# lt_mikro_workshop.net
KiCad netlist of a schematic drawn in EAGLE
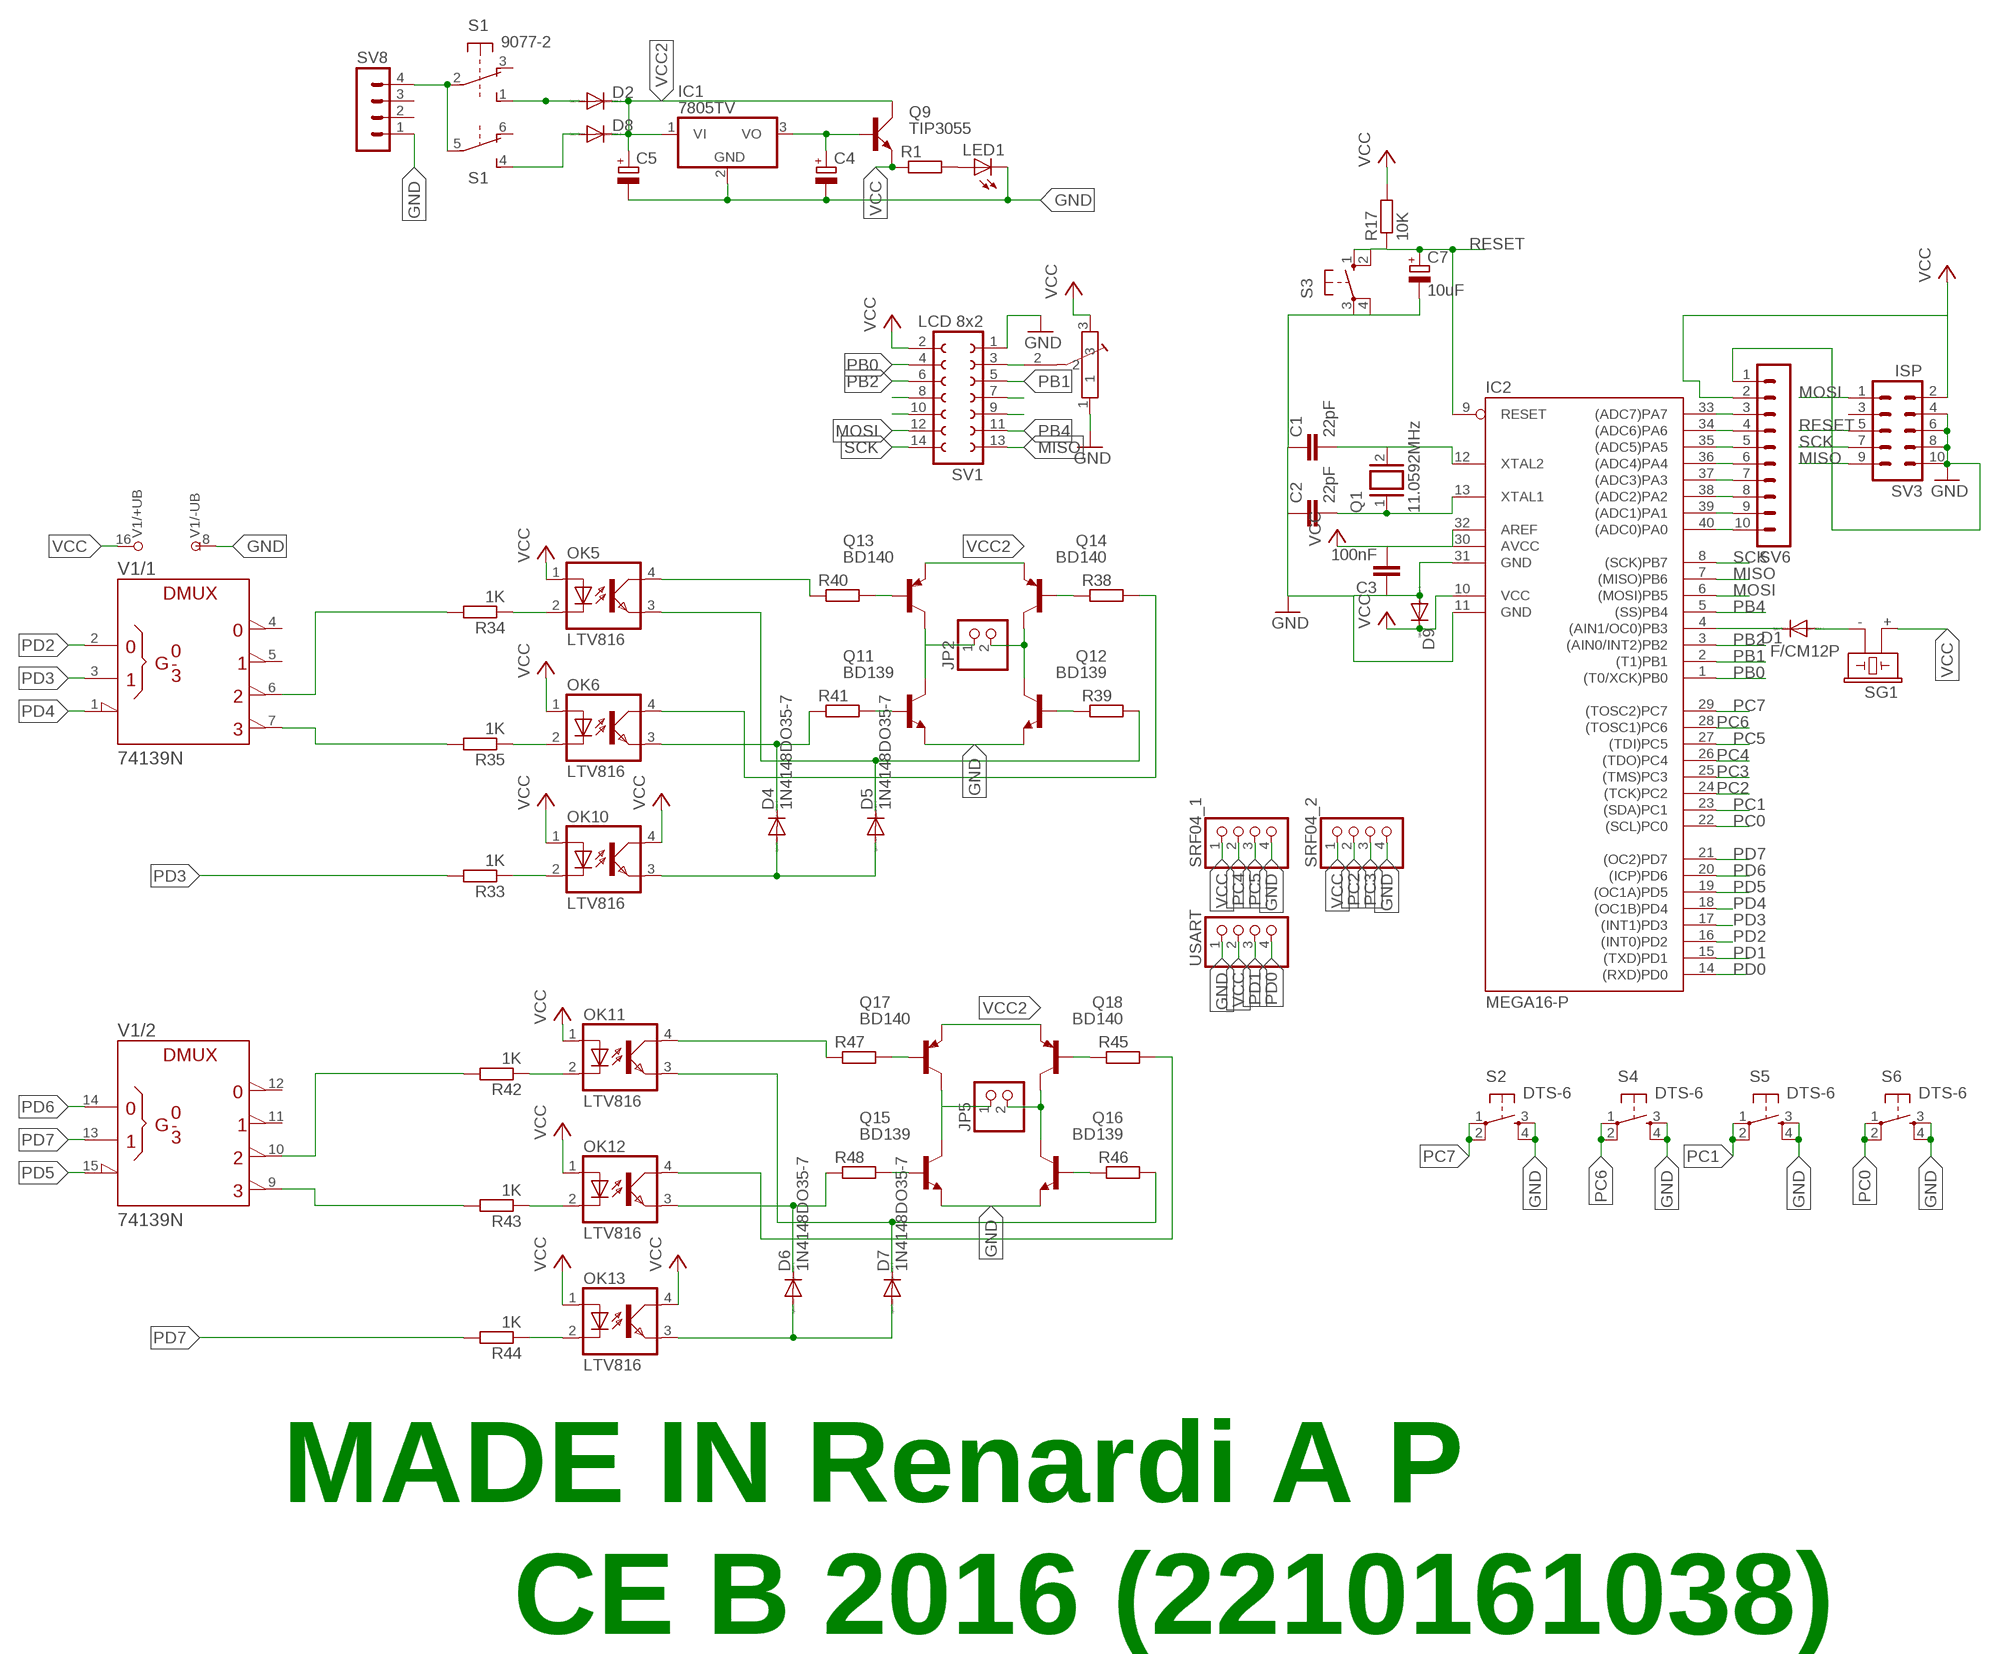
[diagram p0: schematic, sheet 1]

(export (version "E")
  (design (tool "Eeschema 10.0.6"))
  (components
    (comp (ref "C1")
      (value "22pF")
      (footprint "eagle-import:C2.5-2")
      (libsource (lib "eagle-import") (part "C2.5/2"))
    )
    (comp (ref "C2")
      (value "22pF")
      (footprint "eagle-import:C2.5-2")
      (libsource (lib "eagle-import") (part "C2.5/2"))
    )
    (comp (ref "C3")
      (value "100nF")
      (footprint "eagle-import:C2.5-2")
      (libsource (lib "eagle-import") (part "C2.5/2"))
    )
    (comp (ref "C4")
      (value "CPOL-EUE3.5-10")
      (footprint "eagle-import:E3,5-10")
      (libsource (lib "eagle-import") (part "CPOL-EUE3.5-10"))
    )
    (comp (ref "C5")
      (value "CPOL-EUE3.5-10")
      (footprint "eagle-import:E3,5-10")
      (libsource (lib "eagle-import") (part "CPOL-EUE3.5-10"))
    )
    (comp (ref "C7")
      (value "10uF")
      (footprint "eagle-import:E2-5")
      (libsource (lib "eagle-import") (part "CPOL-EUE2-5"))
    )
    (comp (ref "D1")
      (value "DIODE-DO214AA")
      (footprint "eagle-import:DO214AA")
      (libsource (lib "eagle-import") (part "DIODE-DO214AA"))
    )
    (comp (ref "D2")
      (value "DIODE-DO214AA")
      (footprint "eagle-import:DO214AA")
      (libsource (lib "eagle-import") (part "DIODE-DO214AA"))
    )
    (comp (ref "D4")
      (value "1N4148DO35-7")
      (footprint "eagle-import:DO35-7")
      (libsource (lib "eagle-import") (part "1N4148DO35-7"))
    )
    (comp (ref "D5")
      (value "1N4148DO35-7")
      (footprint "eagle-import:DO35-7")
      (libsource (lib "eagle-import") (part "1N4148DO35-7"))
    )
    (comp (ref "D6")
      (value "1N4148DO35-7")
      (footprint "eagle-import:DO35-7")
      (libsource (lib "eagle-import") (part "1N4148DO35-7"))
    )
    (comp (ref "D7")
      (value "1N4148DO35-7")
      (footprint "eagle-import:DO35-7")
      (libsource (lib "eagle-import") (part "1N4148DO35-7"))
    )
    (comp (ref "D8")
      (value "DIODE-DO214AA")
      (footprint "eagle-import:DO214AA")
      (libsource (lib "eagle-import") (part "DIODE-DO214AA"))
    )
    (comp (ref "D9")
      (value "DIODE-DO214AA")
      (footprint "eagle-import:DO214AA")
      (libsource (lib "eagle-import") (part "DIODE-DO214AA"))
    )
    (comp (ref "IC1")
      (value "7805TV")
      (footprint "eagle-import:TO220V")
      (libsource (lib "eagle-import") (part "78TV05"))
    )
    (comp (ref "IC2")
      (value "MEGA16-P")
      (footprint "eagle-import:DIL40")
      (libsource (lib "eagle-import") (part "MEGA16-P"))
    )
    (comp (ref "JP2")
      (value "PINHD-1X2")
      (footprint "eagle-import:1X02")
      (libsource (lib "eagle-import") (part "PINHD-1X2"))
    )
    (comp (ref "JP5")
      (value "PINHD-1X2")
      (footprint "eagle-import:1X02")
      (libsource (lib "eagle-import") (part "PINHD-1X2"))
    )
    (comp (ref "LED1")
      (value "LED3MM")
      (footprint "eagle-import:LED3MM")
      (libsource (lib "eagle-import") (part "LED3MM"))
    )
    (comp (ref "OK5")
      (value "LTV816")
      (footprint "eagle-import:DIL04")
      (libsource (lib "eagle-import") (part "LTV816"))
    )
    (comp (ref "OK6")
      (value "LTV816")
      (footprint "eagle-import:DIL04")
      (libsource (lib "eagle-import") (part "LTV816"))
    )
    (comp (ref "OK10")
      (value "LTV816")
      (footprint "eagle-import:DIL04")
      (libsource (lib "eagle-import") (part "LTV816"))
    )
    (comp (ref "OK11")
      (value "LTV816")
      (footprint "eagle-import:DIL04")
      (libsource (lib "eagle-import") (part "LTV816"))
    )
    (comp (ref "OK12")
      (value "LTV816")
      (footprint "eagle-import:DIL04")
      (libsource (lib "eagle-import") (part "LTV816"))
    )
    (comp (ref "OK13")
      (value "LTV816")
      (footprint "eagle-import:DIL04")
      (libsource (lib "eagle-import") (part "LTV816"))
    )
    (comp (ref "Q1")
      (value "11.0592MHz")
      (footprint "eagle-import:QS")
      (libsource (lib "eagle-import") (part "XTAL/S"))
    )
    (comp (ref "Q9")
      (value "TIP3055")
      (footprint "eagle-import:TOP3AV")
      (libsource (lib "eagle-import") (part "TIP3055"))
    )
    (comp (ref "Q11")
      (value "BD139")
      (footprint "eagle-import:TO126")
      (libsource (lib "eagle-import") (part "BD139"))
    )
    (comp (ref "Q12")
      (value "BD139")
      (footprint "eagle-import:TO126")
      (libsource (lib "eagle-import") (part "BD139"))
    )
    (comp (ref "Q13")
      (value "BD140")
      (footprint "eagle-import:TO126")
      (libsource (lib "eagle-import") (part "BD140"))
    )
    (comp (ref "Q14")
      (value "BD140")
      (footprint "eagle-import:TO126")
      (libsource (lib "eagle-import") (part "BD140"))
    )
    (comp (ref "Q15")
      (value "BD139")
      (footprint "eagle-import:TO126")
      (libsource (lib "eagle-import") (part "BD139"))
    )
    (comp (ref "Q16")
      (value "BD139")
      (footprint "eagle-import:TO126")
      (libsource (lib "eagle-import") (part "BD139"))
    )
    (comp (ref "Q17")
      (value "BD140")
      (footprint "eagle-import:TO126")
      (libsource (lib "eagle-import") (part "BD140"))
    )
    (comp (ref "Q18")
      (value "BD140")
      (footprint "eagle-import:TO126")
      (libsource (lib "eagle-import") (part "BD140"))
    )
    (comp (ref "R1")
      (value "R-EU_0207/7")
      (footprint "eagle-import:0207_7")
      (libsource (lib "eagle-import") (part "R-EU_0207/7"))
    )
    (comp (ref "R17")
      (value "10K")
      (footprint "eagle-import:0204_7")
      (libsource (lib "eagle-import") (part "R-EU_0204/7"))
    )
    (comp (ref "R33")
      (value "1K")
      (footprint "eagle-import:0204_7")
      (libsource (lib "eagle-import") (part "R-EU_0204/7"))
    )
    (comp (ref "R34")
      (value "1K")
      (footprint "eagle-import:0204_7")
      (libsource (lib "eagle-import") (part "R-EU_0204/7"))
    )
    (comp (ref "R35")
      (value "1K")
      (footprint "eagle-import:0204_7")
      (libsource (lib "eagle-import") (part "R-EU_0204/7"))
    )
    (comp (ref "R38")
      (value "R-EU_0207/7")
      (footprint "eagle-import:0207_7")
      (libsource (lib "eagle-import") (part "R-EU_0207/7"))
    )
    (comp (ref "R39")
      (value "R-EU_0207/7")
      (footprint "eagle-import:0207_7")
      (libsource (lib "eagle-import") (part "R-EU_0207/7"))
    )
    (comp (ref "R40")
      (value "R-EU_0207/7")
      (footprint "eagle-import:0207_7")
      (libsource (lib "eagle-import") (part "R-EU_0207/7"))
    )
    (comp (ref "R41")
      (value "R-EU_0207/7")
      (footprint "eagle-import:0207_7")
      (libsource (lib "eagle-import") (part "R-EU_0207/7"))
    )
    (comp (ref "R42")
      (value "1K")
      (footprint "eagle-import:0204_7")
      (libsource (lib "eagle-import") (part "R-EU_0204/7"))
    )
    (comp (ref "R43")
      (value "1K")
      (footprint "eagle-import:0204_7")
      (libsource (lib "eagle-import") (part "R-EU_0204/7"))
    )
    (comp (ref "R44")
      (value "1K")
      (footprint "eagle-import:0204_7")
      (libsource (lib "eagle-import") (part "R-EU_0204/7"))
    )
    (comp (ref "R45")
      (value "R-EU_0207/7")
      (footprint "eagle-import:0207_7")
      (libsource (lib "eagle-import") (part "R-EU_0207/7"))
    )
    (comp (ref "R46")
      (value "R-EU_0207/7")
      (footprint "eagle-import:0207_7")
      (libsource (lib "eagle-import") (part "R-EU_0207/7"))
    )
    (comp (ref "R47")
      (value "R-EU_0207/7")
      (footprint "eagle-import:0207_7")
      (libsource (lib "eagle-import") (part "R-EU_0207/7"))
    )
    (comp (ref "R48")
      (value "R-EU_0207/7")
      (footprint "eagle-import:0207_7")
      (libsource (lib "eagle-import") (part "R-EU_0207/7"))
    )
    (comp (ref "S1")
      (value "9077-2")
      (footprint "eagle-import:9077-2")
      (libsource (lib "eagle-import") (part "9077-2"))
    )
    (comp (ref "S2")
      (value "DTS-6")
      (footprint "eagle-import:DTS-6")
      (libsource (lib "eagle-import") (part "DTS-6"))
    )
    (comp (ref "S3")
      (value "10-XX")
      (footprint "eagle-import:B3F-10XX")
      (libsource (lib "eagle-import") (part "10-XX"))
    )
    (comp (ref "S4")
      (value "DTS-6")
      (footprint "eagle-import:DTS-6")
      (libsource (lib "eagle-import") (part "DTS-6"))
    )
    (comp (ref "S5")
      (value "DTS-6")
      (footprint "eagle-import:DTS-6")
      (libsource (lib "eagle-import") (part "DTS-6"))
    )
    (comp (ref "S6")
      (value "DTS-6")
      (footprint "eagle-import:DTS-6")
      (libsource (lib "eagle-import") (part "DTS-6"))
    )
    (comp (ref "SG1")
      (value "F/CM12P")
      (footprint "eagle-import:F_CM12P")
      (libsource (lib "eagle-import") (part "F/CM12P"))
    )
    (comp (ref "SRF04_1")
      (value "PINHD-1X4")
      (footprint "eagle-import:1X04")
      (libsource (lib "eagle-import") (part "PINHD-1X4"))
    )
    (comp (ref "SRF04_2")
      (value "PINHD-1X4")
      (footprint "eagle-import:1X04")
      (libsource (lib "eagle-import") (part "PINHD-1X4"))
    )
    (comp (ref "SV1")
      (value "LCD 8x2")
      (footprint "eagle-import:FE07-2")
      (libsource (lib "eagle-import") (part "FE07-2"))
    )
    (comp (ref "SV3")
      (value "ISP")
      (footprint "eagle-import:MA05-2")
      (libsource (lib "eagle-import") (part "MA05-2"))
    )
    (comp (ref "SV6")
      (value "MA10-1")
      (footprint "eagle-import:MA10-1")
      (libsource (lib "eagle-import") (part "MA10-1"))
    )
    (comp (ref "SV8")
      (value "MA04-1")
      (footprint "eagle-import:MA04-1")
      (libsource (lib "eagle-import") (part "MA04-1"))
    )
    (comp (ref "U$1")
      (value "TRIMPOT")
      (footprint "eagle-import:TRIMPOT")
      (libsource (lib "eagle-import") (part "TRIMPOT"))
    )
    (comp (ref "USART")
      (value "PINHD-1X4")
      (footprint "eagle-import:1X04")
      (libsource (lib "eagle-import") (part "PINHD-1X4"))
    )
    (comp (ref "V1")
      (value "74139N")
      (footprint "eagle-import:DIL16")
      (libsource (lib "eagle-import") (part "74139N"))
    )
  )
  (nets
    (net (code "1") (name "/RESET") (class "Default")
      (node (ref "C7") (pin "+") (pinfunction "+_+") (pintype "passive"))
      (node (ref "IC2") (pin "9") (pinfunction "RESET_9") (pintype "input"))
      (node (ref "R17") (pin "1") (pinfunction "1_1") (pintype "passive"))
      (node (ref "S3") (pin "1") (pinfunction "S_1") (pintype "passive"))
      (node (ref "S3") (pin "2") (pinfunction "S1_2") (pintype "passive"))
      (node (ref "SV3") (pin "5") (pinfunction "5_5") (pintype "passive"))
    )
    (net (code "2") (name "GND") (class "Default")
      (node (ref "C1") (pin "1") (pinfunction "1_1") (pintype "passive"))
      (node (ref "C2") (pin "1") (pinfunction "1_1") (pintype "passive"))
      (node (ref "C3") (pin "1") (pinfunction "1_1") (pintype "passive"))
      (node (ref "C4") (pin "-") (pinfunction "-_-") (pintype "passive"))
      (node (ref "C5") (pin "-") (pinfunction "-_-") (pintype "passive"))
      (node (ref "C7") (pin "-") (pinfunction "-_-") (pintype "passive"))
      (node (ref "D9") (pin "A") (pinfunction "A_A") (pintype "passive"))
      (node (ref "IC1") (pin "2") (pinfunction "GND_2") (pintype "passive"))
      (node (ref "IC2") (pin "11") (pinfunction "GND_11") (pintype "power_in"))
      (node (ref "IC2") (pin "31") (pinfunction "GND_31") (pintype "power_in"))
      (node (ref "LED1") (pin "K") (pinfunction "C_K") (pintype "passive"))
      (node (ref "Q11") (pin "1") (pinfunction "E_1") (pintype "passive"))
      (node (ref "Q12") (pin "1") (pinfunction "E_1") (pintype "passive"))
      (node (ref "Q15") (pin "1") (pinfunction "E_1") (pintype "passive"))
      (node (ref "Q16") (pin "1") (pinfunction "E_1") (pintype "passive"))
      (node (ref "S2") (pin "3") (pinfunction "3_3") (pintype "passive"))
      (node (ref "S2") (pin "4") (pinfunction "4_4") (pintype "passive"))
      (node (ref "S3") (pin "3") (pinfunction "P_3") (pintype "passive"))
      (node (ref "S3") (pin "4") (pinfunction "P1_4") (pintype "passive"))
      (node (ref "S4") (pin "3") (pinfunction "3_3") (pintype "passive"))
      (node (ref "S4") (pin "4") (pinfunction "4_4") (pintype "passive"))
      (node (ref "S5") (pin "3") (pinfunction "3_3") (pintype "passive"))
      (node (ref "S5") (pin "4") (pinfunction "4_4") (pintype "passive"))
      (node (ref "S6") (pin "3") (pinfunction "3_3") (pintype "passive"))
      (node (ref "S6") (pin "4") (pinfunction "4_4") (pintype "passive"))
      (node (ref "SRF04_1") (pin "4") (pinfunction "4_4") (pintype "passive"))
      (node (ref "SRF04_2") (pin "4") (pinfunction "4_4") (pintype "passive"))
      (node (ref "SV1") (pin "1") (pinfunction "1_1") (pintype "passive"))
      (node (ref "SV3") (pin "10") (pinfunction "10_10") (pintype "passive"))
      (node (ref "SV3") (pin "4") (pinfunction "4_4") (pintype "passive"))
      (node (ref "SV3") (pin "6") (pinfunction "6_6") (pintype "passive"))
      (node (ref "SV3") (pin "8") (pinfunction "8_8") (pintype "passive"))
      (node (ref "SV6") (pin "1") (pinfunction "1_1") (pintype "passive"))
      (node (ref "SV8") (pin "1") (pinfunction "1_1") (pintype "passive"))
      (node (ref "U$1") (pin "1") (pinfunction "1_1") (pintype "bidirectional"))
      (node (ref "USART") (pin "1") (pinfunction "1_1") (pintype "passive"))
      (node (ref "V1") (pin "8") (pinfunction "-UB_8") (pintype "power_in"))
    )
    (net (code "3") (name "MISO") (class "Default")
      (node (ref "IC2") (pin "7") (pinfunction "(MISO)PB6_7") (pintype "bidirectional"))
      (node (ref "SV1") (pin "13") (pinfunction "13_13") (pintype "passive"))
      (node (ref "SV3") (pin "9") (pinfunction "9_9") (pintype "passive"))
    )
    (net (code "4") (name "MOSI") (class "Default")
      (node (ref "IC2") (pin "6") (pinfunction "(MOSI)PB5_6") (pintype "bidirectional"))
      (node (ref "SV1") (pin "12") (pinfunction "12_12") (pintype "passive"))
      (node (ref "SV3") (pin "1") (pinfunction "1_1") (pintype "passive"))
    )
    (net (code "5") (name "Net-(IC1-VO)") (class "Default")
      (node (ref "C4") (pin "+") (pinfunction "+_+") (pintype "passive"))
      (node (ref "IC1") (pin "3") (pinfunction "VO_3") (pintype "passive"))
      (node (ref "Q9") (pin "B") (pinfunction "B_B") (pintype "passive"))
    )
    (net (code "6") (name "Net-(IC2-(ADC0)PA0)") (class "Default")
      (node (ref "IC2") (pin "40") (pinfunction "(ADC0)PA0_40") (pintype "bidirectional"))
      (node (ref "SV6") (pin "10") (pinfunction "10_10") (pintype "passive"))
    )
    (net (code "7") (name "Net-(IC2-(ADC1)PA1)") (class "Default")
      (node (ref "IC2") (pin "39") (pinfunction "(ADC1)PA1_39") (pintype "bidirectional"))
      (node (ref "SV6") (pin "9") (pinfunction "9_9") (pintype "passive"))
    )
    (net (code "8") (name "Net-(IC2-(ADC2)PA2)") (class "Default")
      (node (ref "IC2") (pin "38") (pinfunction "(ADC2)PA2_38") (pintype "bidirectional"))
      (node (ref "SV6") (pin "8") (pinfunction "8_8") (pintype "passive"))
    )
    (net (code "9") (name "Net-(IC2-(ADC3)PA3)") (class "Default")
      (node (ref "IC2") (pin "37") (pinfunction "(ADC3)PA3_37") (pintype "bidirectional"))
      (node (ref "SV6") (pin "7") (pinfunction "7_7") (pintype "passive"))
    )
    (net (code "10") (name "Net-(IC2-(ADC4)PA4)") (class "Default")
      (node (ref "IC2") (pin "36") (pinfunction "(ADC4)PA4_36") (pintype "bidirectional"))
      (node (ref "SV6") (pin "6") (pinfunction "6_6") (pintype "passive"))
    )
    (net (code "11") (name "Net-(IC2-(ADC5)PA5)") (class "Default")
      (node (ref "IC2") (pin "35") (pinfunction "(ADC5)PA5_35") (pintype "bidirectional"))
      (node (ref "SV6") (pin "5") (pinfunction "5_5") (pintype "passive"))
    )
    (net (code "12") (name "Net-(IC2-(ADC6)PA6)") (class "Default")
      (node (ref "IC2") (pin "34") (pinfunction "(ADC6)PA6_34") (pintype "bidirectional"))
      (node (ref "SV6") (pin "4") (pinfunction "4_4") (pintype "passive"))
    )
    (net (code "13") (name "Net-(IC2-(ADC7)PA7)") (class "Default")
      (node (ref "IC2") (pin "33") (pinfunction "(ADC7)PA7_33") (pintype "bidirectional"))
      (node (ref "SV6") (pin "3") (pinfunction "3_3") (pintype "passive"))
    )
    (net (code "14") (name "Net-(IC2-(AIN1{slash}OC0)PB3)") (class "Default")
      (node (ref "D1") (pin "C") (pinfunction "C_C") (pintype "passive"))
      (node (ref "IC2") (pin "4") (pinfunction "(AIN1/OC0)PB3_4") (pintype "bidirectional"))
    )
    (net (code "15") (name "Net-(IC2-XTAL1)") (class "Default")
      (node (ref "C2") (pin "2") (pinfunction "2_2") (pintype "passive"))
      (node (ref "IC2") (pin "13") (pinfunction "XTAL1_13") (pintype "bidirectional"))
      (node (ref "Q1") (pin "1") (pinfunction "1_1") (pintype "passive"))
    )
    (net (code "16") (name "Net-(IC2-XTAL2)") (class "Default")
      (node (ref "C1") (pin "2") (pinfunction "2_2") (pintype "passive"))
      (node (ref "IC2") (pin "12") (pinfunction "XTAL2_12") (pintype "bidirectional"))
      (node (ref "Q1") (pin "2") (pinfunction "2_2") (pintype "passive"))
    )
    (net (code "17") (name "Net-(LED1-PadA)") (class "Default")
      (node (ref "LED1") (pin "A") (pinfunction "A_A") (pintype "passive"))
      (node (ref "R1") (pin "2") (pinfunction "2_2") (pintype "passive"))
    )
    (net (code "18") (name "Net-(OK5-C)") (class "Default")
      (node (ref "OK5") (pin "2") (pinfunction "C_2") (pintype "passive"))
      (node (ref "R34") (pin "1") (pinfunction "1_1") (pintype "passive"))
    )
    (net (code "19") (name "Net-(OK5-COL)") (class "Default")
      (node (ref "OK5") (pin "4") (pinfunction "COL_4") (pintype "passive"))
      (node (ref "R40") (pin "1") (pinfunction "1_1") (pintype "passive"))
    )
    (net (code "20") (name "Net-(OK5-EMIT)") (class "Default")
      (node (ref "D5") (pin "C") (pinfunction "C_C") (pintype "passive"))
      (node (ref "OK5") (pin "3") (pinfunction "EMIT_3") (pintype "passive"))
      (node (ref "R39") (pin "2") (pinfunction "2_2") (pintype "passive"))
    )
    (net (code "21") (name "Net-(OK6-C)") (class "Default")
      (node (ref "OK6") (pin "2") (pinfunction "C_2") (pintype "passive"))
      (node (ref "R35") (pin "1") (pinfunction "1_1") (pintype "passive"))
    )
    (net (code "22") (name "Net-(OK6-COL)") (class "Default")
      (node (ref "OK6") (pin "4") (pinfunction "COL_4") (pintype "passive"))
      (node (ref "R38") (pin "2") (pinfunction "2_2") (pintype "passive"))
    )
    (net (code "23") (name "Net-(OK6-EMIT)") (class "Default")
      (node (ref "D4") (pin "C") (pinfunction "C_C") (pintype "passive"))
      (node (ref "OK6") (pin "3") (pinfunction "EMIT_3") (pintype "passive"))
      (node (ref "R41") (pin "1") (pinfunction "1_1") (pintype "passive"))
    )
    (net (code "24") (name "Net-(OK10-C)") (class "Default")
      (node (ref "OK10") (pin "2") (pinfunction "C_2") (pintype "passive"))
      (node (ref "R33") (pin "1") (pinfunction "1_1") (pintype "passive"))
    )
    (net (code "25") (name "Net-(OK10-EMIT)") (class "Default")
      (node (ref "D4") (pin "A") (pinfunction "A_A") (pintype "passive"))
      (node (ref "D5") (pin "A") (pinfunction "A_A") (pintype "passive"))
      (node (ref "OK10") (pin "3") (pinfunction "EMIT_3") (pintype "passive"))
    )
    (net (code "26") (name "Net-(OK11-C)") (class "Default")
      (node (ref "OK11") (pin "2") (pinfunction "C_2") (pintype "passive"))
      (node (ref "R42") (pin "1") (pinfunction "1_1") (pintype "passive"))
    )
    (net (code "27") (name "Net-(OK11-COL)") (class "Default")
      (node (ref "OK11") (pin "4") (pinfunction "COL_4") (pintype "passive"))
      (node (ref "R47") (pin "1") (pinfunction "1_1") (pintype "passive"))
    )
    (net (code "28") (name "Net-(OK11-EMIT)") (class "Default")
      (node (ref "D7") (pin "C") (pinfunction "C_C") (pintype "passive"))
      (node (ref "OK11") (pin "3") (pinfunction "EMIT_3") (pintype "passive"))
      (node (ref "R46") (pin "2") (pinfunction "2_2") (pintype "passive"))
    )
    (net (code "29") (name "Net-(OK12-C)") (class "Default")
      (node (ref "OK12") (pin "2") (pinfunction "C_2") (pintype "passive"))
      (node (ref "R43") (pin "1") (pinfunction "1_1") (pintype "passive"))
    )
    (net (code "30") (name "Net-(OK12-COL)") (class "Default")
      (node (ref "OK12") (pin "4") (pinfunction "COL_4") (pintype "passive"))
      (node (ref "R45") (pin "2") (pinfunction "2_2") (pintype "passive"))
    )
    (net (code "31") (name "Net-(OK12-EMIT)") (class "Default")
      (node (ref "D6") (pin "C") (pinfunction "C_C") (pintype "passive"))
      (node (ref "OK12") (pin "3") (pinfunction "EMIT_3") (pintype "passive"))
      (node (ref "R48") (pin "1") (pinfunction "1_1") (pintype "passive"))
    )
    (net (code "32") (name "Net-(OK13-C)") (class "Default")
      (node (ref "OK13") (pin "2") (pinfunction "C_2") (pintype "passive"))
      (node (ref "R44") (pin "1") (pinfunction "1_1") (pintype "passive"))
    )
    (net (code "33") (name "Net-(OK13-EMIT)") (class "Default")
      (node (ref "D6") (pin "A") (pinfunction "A_A") (pintype "passive"))
      (node (ref "D7") (pin "A") (pinfunction "A_A") (pintype "passive"))
      (node (ref "OK13") (pin "3") (pinfunction "EMIT_3") (pintype "passive"))
    )
    (net (code "34") (name "Net-(Q11-B)") (class "Default")
      (node (ref "Q11") (pin "3") (pinfunction "B_3") (pintype "passive"))
      (node (ref "R41") (pin "2") (pinfunction "2_2") (pintype "passive"))
    )
    (net (code "35") (name "Net-(Q11-C)") (class "Default")
      (node (ref "JP2") (pin "1") (pinfunction "1_1") (pintype "passive"))
      (node (ref "Q11") (pin "2") (pinfunction "C_2") (pintype "passive"))
      (node (ref "Q13") (pin "2") (pinfunction "C_2") (pintype "passive"))
    )
    (net (code "36") (name "Net-(Q12-B)") (class "Default")
      (node (ref "Q12") (pin "3") (pinfunction "B_3") (pintype "passive"))
      (node (ref "R39") (pin "1") (pinfunction "1_1") (pintype "passive"))
    )
    (net (code "37") (name "Net-(Q12-C)") (class "Default")
      (node (ref "JP2") (pin "2") (pinfunction "2_2") (pintype "passive"))
      (node (ref "Q12") (pin "2") (pinfunction "C_2") (pintype "passive"))
      (node (ref "Q14") (pin "2") (pinfunction "C_2") (pintype "passive"))
    )
    (net (code "38") (name "Net-(Q13-B)") (class "Default")
      (node (ref "Q13") (pin "3") (pinfunction "B_3") (pintype "passive"))
      (node (ref "R40") (pin "2") (pinfunction "2_2") (pintype "passive"))
    )
    (net (code "39") (name "Net-(Q14-B)") (class "Default")
      (node (ref "Q14") (pin "3") (pinfunction "B_3") (pintype "passive"))
      (node (ref "R38") (pin "1") (pinfunction "1_1") (pintype "passive"))
    )
    (net (code "40") (name "Net-(Q15-B)") (class "Default")
      (node (ref "Q15") (pin "3") (pinfunction "B_3") (pintype "passive"))
      (node (ref "R48") (pin "2") (pinfunction "2_2") (pintype "passive"))
    )
    (net (code "41") (name "Net-(Q15-C)") (class "Default")
      (node (ref "JP5") (pin "1") (pinfunction "1_1") (pintype "passive"))
      (node (ref "Q15") (pin "2") (pinfunction "C_2") (pintype "passive"))
      (node (ref "Q17") (pin "2") (pinfunction "C_2") (pintype "passive"))
    )
    (net (code "42") (name "Net-(Q16-B)") (class "Default")
      (node (ref "Q16") (pin "3") (pinfunction "B_3") (pintype "passive"))
      (node (ref "R46") (pin "1") (pinfunction "1_1") (pintype "passive"))
    )
    (net (code "43") (name "Net-(Q16-C)") (class "Default")
      (node (ref "JP5") (pin "2") (pinfunction "2_2") (pintype "passive"))
      (node (ref "Q16") (pin "2") (pinfunction "C_2") (pintype "passive"))
      (node (ref "Q18") (pin "2") (pinfunction "C_2") (pintype "passive"))
    )
    (net (code "44") (name "Net-(Q17-B)") (class "Default")
      (node (ref "Q17") (pin "3") (pinfunction "B_3") (pintype "passive"))
      (node (ref "R47") (pin "2") (pinfunction "2_2") (pintype "passive"))
    )
    (net (code "45") (name "Net-(Q18-B)") (class "Default")
      (node (ref "Q18") (pin "3") (pinfunction "B_3") (pintype "passive"))
      (node (ref "R45") (pin "1") (pinfunction "1_1") (pintype "passive"))
    )
    (net (code "46") (name "Net-(S1A-P)") (class "Default")
      (node (ref "S1") (pin "2") (pinfunction "P_2") (pintype "passive"))
      (node (ref "S1") (pin "5") (pinfunction "P_5") (pintype "passive"))
      (node (ref "SV8") (pin "4") (pinfunction "4_4") (pintype "passive"))
    )
    (net (code "47") (name "Net-(S1A-S)") (class "Default")
      (node (ref "D2") (pin "A") (pinfunction "A_A") (pintype "passive"))
      (node (ref "S1") (pin "1") (pinfunction "S_1") (pintype "passive"))
    )
    (net (code "48") (name "Net-(S1B-S)") (class "Default")
      (node (ref "D8") (pin "A") (pinfunction "A_A") (pintype "passive"))
      (node (ref "S1") (pin "4") (pinfunction "S_4") (pintype "passive"))
    )
    (net (code "49") (name "Net-(SG1-2)") (class "Default")
      (node (ref "D1") (pin "A") (pinfunction "A_A") (pintype "passive"))
      (node (ref "SG1") (pin "-") (pinfunction "2_-") (pintype "passive"))
    )
    (net (code "50") (name "Net-(V1C-Y2)") (class "Default")
      (node (ref "R34") (pin "2") (pinfunction "2_2") (pintype "passive"))
      (node (ref "V1") (pin "6") (pinfunction "Y2_6") (pintype "output"))
    )
    (net (code "51") (name "Net-(V1C-Y3)") (class "Default")
      (node (ref "R35") (pin "2") (pinfunction "2_2") (pintype "passive"))
      (node (ref "V1") (pin "7") (pinfunction "Y3_7") (pintype "output"))
    )
    (net (code "52") (name "Net-(V1D-Y2)") (class "Default")
      (node (ref "R42") (pin "2") (pinfunction "2_2") (pintype "passive"))
      (node (ref "V1") (pin "10") (pinfunction "Y2_10") (pintype "output"))
    )
    (net (code "53") (name "Net-(V1D-Y3)") (class "Default")
      (node (ref "R43") (pin "2") (pinfunction "2_2") (pintype "passive"))
      (node (ref "V1") (pin "9") (pinfunction "Y3_9") (pintype "output"))
    )
    (net (code "54") (name "PB0") (class "Default")
      (node (ref "IC2") (pin "1") (pinfunction "(T0/XCK)PB0_1") (pintype "bidirectional"))
      (node (ref "SV1") (pin "3") (pinfunction "3_3") (pintype "passive"))
      (node (ref "SV1") (pin "4") (pinfunction "4_4") (pintype "passive"))
      (node (ref "U$1") (pin "2") (pinfunction "2_2") (pintype "bidirectional"))
    )
    (net (code "55") (name "PB1") (class "Default")
      (node (ref "IC2") (pin "2") (pinfunction "(T1)PB1_2") (pintype "bidirectional"))
      (node (ref "SV1") (pin "5") (pinfunction "5_5") (pintype "passive"))
    )
    (net (code "56") (name "PB2") (class "Default")
      (node (ref "IC2") (pin "3") (pinfunction "(AIN0/INT2)PB2_3") (pintype "bidirectional"))
      (node (ref "SV1") (pin "6") (pinfunction "6_6") (pintype "passive"))
    )
    (net (code "57") (name "PB4") (class "Default")
      (node (ref "IC2") (pin "5") (pinfunction "(SS)PB4_5") (pintype "bidirectional"))
      (node (ref "SV1") (pin "11") (pinfunction "11_11") (pintype "passive"))
    )
    (net (code "58") (name "PC0") (class "Default")
      (node (ref "IC2") (pin "22") (pinfunction "(SCL)PC0_22") (pintype "bidirectional"))
      (node (ref "S6") (pin "1") (pinfunction "1_1") (pintype "passive"))
      (node (ref "S6") (pin "2") (pinfunction "2_2") (pintype "passive"))
    )
    (net (code "59") (name "PC1") (class "Default")
      (node (ref "IC2") (pin "23") (pinfunction "(SDA)PC1_23") (pintype "bidirectional"))
      (node (ref "S5") (pin "1") (pinfunction "1_1") (pintype "passive"))
      (node (ref "S5") (pin "2") (pinfunction "2_2") (pintype "passive"))
    )
    (net (code "60") (name "PC2") (class "Default")
      (node (ref "IC2") (pin "24") (pinfunction "(TCK)PC2_24") (pintype "bidirectional"))
      (node (ref "SRF04_2") (pin "2") (pinfunction "2_2") (pintype "passive"))
    )
    (net (code "61") (name "PC3") (class "Default")
      (node (ref "IC2") (pin "25") (pinfunction "(TMS)PC3_25") (pintype "bidirectional"))
      (node (ref "SRF04_2") (pin "3") (pinfunction "3_3") (pintype "passive"))
    )
    (net (code "62") (name "PC4") (class "Default")
      (node (ref "IC2") (pin "26") (pinfunction "(TDO)PC4_26") (pintype "bidirectional"))
      (node (ref "SRF04_1") (pin "2") (pinfunction "2_2") (pintype "passive"))
    )
    (net (code "63") (name "PC5") (class "Default")
      (node (ref "IC2") (pin "27") (pinfunction "(TDI)PC5_27") (pintype "bidirectional"))
      (node (ref "SRF04_1") (pin "3") (pinfunction "3_3") (pintype "passive"))
    )
    (net (code "64") (name "PC6") (class "Default")
      (node (ref "IC2") (pin "28") (pinfunction "(TOSC1)PC6_28") (pintype "bidirectional"))
      (node (ref "S4") (pin "1") (pinfunction "1_1") (pintype "passive"))
      (node (ref "S4") (pin "2") (pinfunction "2_2") (pintype "passive"))
    )
    (net (code "65") (name "PC7") (class "Default")
      (node (ref "IC2") (pin "29") (pinfunction "(TOSC2)PC7_29") (pintype "bidirectional"))
      (node (ref "S2") (pin "1") (pinfunction "1_1") (pintype "passive"))
      (node (ref "S2") (pin "2") (pinfunction "2_2") (pintype "passive"))
    )
    (net (code "66") (name "PD0") (class "Default")
      (node (ref "IC2") (pin "14") (pinfunction "(RXD)PD0_14") (pintype "bidirectional"))
      (node (ref "USART") (pin "4") (pinfunction "4_4") (pintype "passive"))
    )
    (net (code "67") (name "PD1") (class "Default")
      (node (ref "IC2") (pin "15") (pinfunction "(TXD)PD1_15") (pintype "bidirectional"))
      (node (ref "USART") (pin "3") (pinfunction "3_3") (pintype "passive"))
    )
    (net (code "68") (name "PD2") (class "Default")
      (node (ref "IC2") (pin "16") (pinfunction "(INT0)PD2_16") (pintype "bidirectional"))
      (node (ref "V1") (pin "2") (pinfunction "A_2") (pintype "input"))
    )
    (net (code "69") (name "PD3") (class "Default")
      (node (ref "IC2") (pin "17") (pinfunction "(INT1)PD3_17") (pintype "bidirectional"))
      (node (ref "R33") (pin "2") (pinfunction "2_2") (pintype "passive"))
      (node (ref "V1") (pin "3") (pinfunction "B_3") (pintype "input"))
    )
    (net (code "70") (name "PD4") (class "Default")
      (node (ref "IC2") (pin "18") (pinfunction "(OC1B)PD4_18") (pintype "bidirectional"))
      (node (ref "V1") (pin "1") (pinfunction "~{G}_1") (pintype "input"))
    )
    (net (code "71") (name "PD5") (class "Default")
      (node (ref "IC2") (pin "19") (pinfunction "(OC1A)PD5_19") (pintype "bidirectional"))
      (node (ref "V1") (pin "15") (pinfunction "~{G}_15") (pintype "input"))
    )
    (net (code "72") (name "PD6") (class "Default")
      (node (ref "IC2") (pin "20") (pinfunction "(ICP)PD6_20") (pintype "bidirectional"))
      (node (ref "V1") (pin "14") (pinfunction "A_14") (pintype "input"))
    )
    (net (code "73") (name "PD7") (class "Default")
      (node (ref "IC2") (pin "21") (pinfunction "(OC2)PD7_21") (pintype "bidirectional"))
      (node (ref "R44") (pin "2") (pinfunction "2_2") (pintype "passive"))
      (node (ref "V1") (pin "13") (pinfunction "B_13") (pintype "input"))
    )
    (net (code "74") (name "SCK") (class "Default")
      (node (ref "IC2") (pin "8") (pinfunction "(SCK)PB7_8") (pintype "bidirectional"))
      (node (ref "SV1") (pin "14") (pinfunction "14_14") (pintype "passive"))
      (node (ref "SV3") (pin "7") (pinfunction "7_7") (pintype "passive"))
    )
    (net (code "75") (name "VCC") (class "Default")
      (node (ref "C3") (pin "2") (pinfunction "2_2") (pintype "passive"))
      (node (ref "D9") (pin "C") (pinfunction "C_C") (pintype "passive"))
      (node (ref "IC2") (pin "10") (pinfunction "VCC_10") (pintype "power_in"))
      (node (ref "IC2") (pin "30") (pinfunction "AVCC_30") (pintype "power_in"))
      (node (ref "IC2") (pin "32") (pinfunction "AREF_32") (pintype "passive"))
      (node (ref "OK10") (pin "1") (pinfunction "A_1") (pintype "passive"))
      (node (ref "OK10") (pin "4") (pinfunction "COL_4") (pintype "passive"))
      (node (ref "OK11") (pin "1") (pinfunction "A_1") (pintype "passive"))
      (node (ref "OK12") (pin "1") (pinfunction "A_1") (pintype "passive"))
      (node (ref "OK13") (pin "1") (pinfunction "A_1") (pintype "passive"))
      (node (ref "OK13") (pin "4") (pinfunction "COL_4") (pintype "passive"))
      (node (ref "OK5") (pin "1") (pinfunction "A_1") (pintype "passive"))
      (node (ref "OK6") (pin "1") (pinfunction "A_1") (pintype "passive"))
      (node (ref "Q9") (pin "E") (pinfunction "E_E") (pintype "passive"))
      (node (ref "R1") (pin "1") (pinfunction "1_1") (pintype "passive"))
      (node (ref "R17") (pin "2") (pinfunction "2_2") (pintype "passive"))
      (node (ref "SG1") (pin "+") (pinfunction "1_+") (pintype "passive"))
      (node (ref "SRF04_1") (pin "1") (pinfunction "1_1") (pintype "passive"))
      (node (ref "SRF04_2") (pin "1") (pinfunction "1_1") (pintype "passive"))
      (node (ref "SV1") (pin "2") (pinfunction "2_2") (pintype "passive"))
      (node (ref "SV3") (pin "2") (pinfunction "2_2") (pintype "passive"))
      (node (ref "SV6") (pin "2") (pinfunction "2_2") (pintype "passive"))
      (node (ref "U$1") (pin "3") (pinfunction "3_3") (pintype "bidirectional"))
      (node (ref "USART") (pin "2") (pinfunction "2_2") (pintype "passive"))
      (node (ref "V1") (pin "16") (pinfunction "+UB_16") (pintype "power_in"))
    )
    (net (code "76") (name "VCC2") (class "Default")
      (node (ref "C5") (pin "+") (pinfunction "+_+") (pintype "passive"))
      (node (ref "D2") (pin "C") (pinfunction "C_C") (pintype "passive"))
      (node (ref "D8") (pin "C") (pinfunction "C_C") (pintype "passive"))
      (node (ref "IC1") (pin "1") (pinfunction "VI_1") (pintype "input"))
      (node (ref "Q13") (pin "1") (pinfunction "E_1") (pintype "passive"))
      (node (ref "Q14") (pin "1") (pinfunction "E_1") (pintype "passive"))
      (node (ref "Q17") (pin "1") (pinfunction "E_1") (pintype "passive"))
      (node (ref "Q18") (pin "1") (pinfunction "E_1") (pintype "passive"))
      (node (ref "Q9") (pin "C") (pinfunction "C_C") (pintype "passive"))
    )
    (net (code "77") (name "unconnected-(S1A-O-Pad3)") (class "Default")
      (node (ref "S1") (pin "3") (pinfunction "O_3") (pintype "passive"))
    )
    (net (code "78") (name "unconnected-(S1B-O-Pad6)") (class "Default")
      (node (ref "S1") (pin "6") (pinfunction "O_6") (pintype "passive"))
    )
    (net (code "79") (name "unconnected-(SV1-Pad7)") (class "Default")
      (node (ref "SV1") (pin "7") (pinfunction "7_7") (pintype "passive"))
    )
    (net (code "80") (name "unconnected-(SV1-Pad8)") (class "Default")
      (node (ref "SV1") (pin "8") (pinfunction "8_8") (pintype "passive"))
    )
    (net (code "81") (name "unconnected-(SV1-Pad9)") (class "Default")
      (node (ref "SV1") (pin "9") (pinfunction "9_9") (pintype "passive"))
    )
    (net (code "82") (name "unconnected-(SV1-Pad10)") (class "Default")
      (node (ref "SV1") (pin "10") (pinfunction "10_10") (pintype "passive"))
    )
    (net (code "83") (name "unconnected-(SV3-Pad3)") (class "Default")
      (node (ref "SV3") (pin "3") (pinfunction "3_3") (pintype "passive"))
    )
    (net (code "84") (name "unconnected-(SV8-Pad2)") (class "Default")
      (node (ref "SV8") (pin "2") (pinfunction "2_2") (pintype "passive"))
    )
    (net (code "85") (name "unconnected-(SV8-Pad3)") (class "Default")
      (node (ref "SV8") (pin "3") (pinfunction "3_3") (pintype "passive"))
    )
    (net (code "86") (name "unconnected-(V1C-Y0-Pad4)") (class "Default")
      (node (ref "V1") (pin "4") (pinfunction "Y0_4") (pintype "output"))
    )
    (net (code "87") (name "unconnected-(V1C-Y1-Pad5)") (class "Default")
      (node (ref "V1") (pin "5") (pinfunction "Y1_5") (pintype "output"))
    )
    (net (code "88") (name "unconnected-(V1D-Y0-Pad12)") (class "Default")
      (node (ref "V1") (pin "12") (pinfunction "Y0_12") (pintype "output"))
    )
    (net (code "89") (name "unconnected-(V1D-Y1-Pad11)") (class "Default")
      (node (ref "V1") (pin "11") (pinfunction "Y1_11") (pintype "output"))
    )
  )
)
